# Video_out.net
KiCad netlist of a schematic drawn in Altium Designer
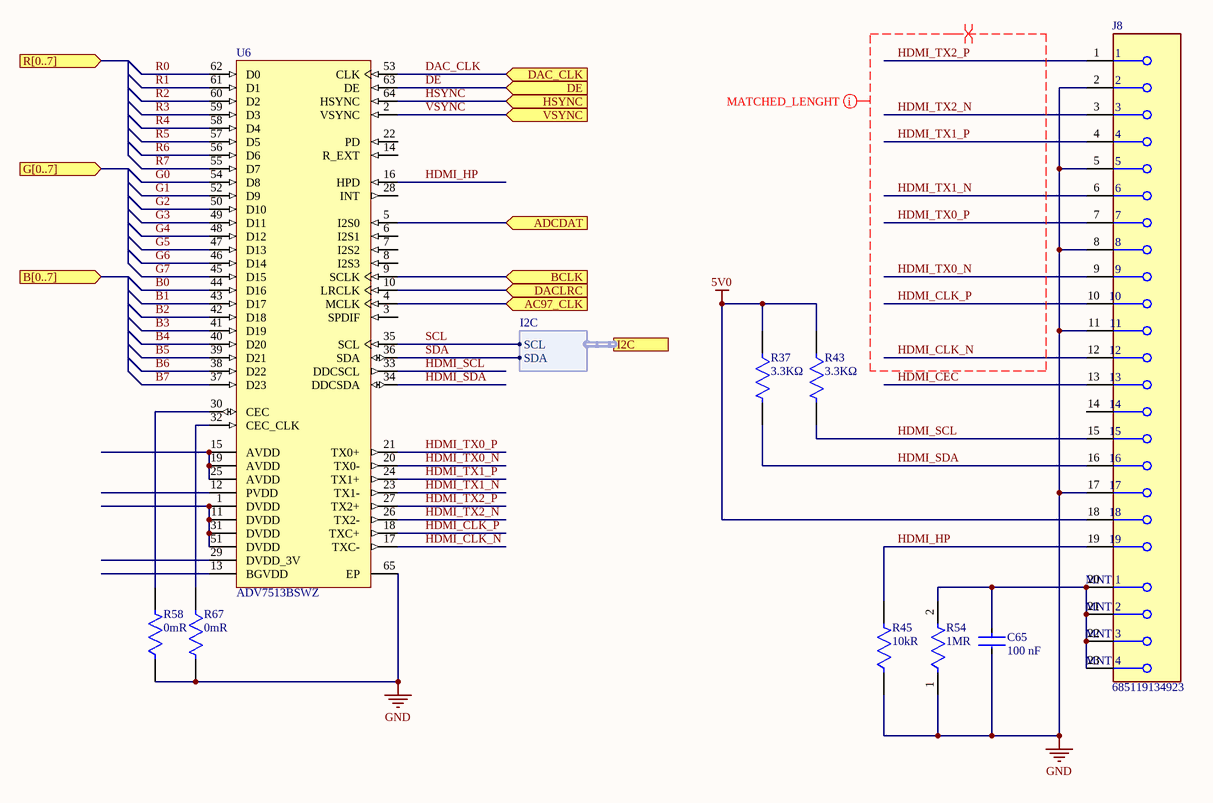
[diagram p0: Video out.SchDoc]

(export (version "E")
  (design (tool "Eeschema 10.0.6"))
  (components
    (comp (ref "C65")
      (value "CC0805KRX7R9BB104")
      (footprint "FP-CC0805-0_85-IPC_A")
      (description "CAP CER 0.1UF 50V X7R 0805")
      (fields (field (name "CAPACITANCE") "100 nF") (field (name "MANUFACTURER") "Yageo"))
      (libsource (lib "SchLib") (part "CMP-2100-03606-3"))
    )
    (comp (ref "J8")
      (value "685119134923")
      (footprint "FP-685119134923-MFG")
      (description "CONN RCPT HDMI 19POS SMD R/A")
      (libsource (lib "Altium Content Vault") (part "e5ff4299a1c525cc9972ed96ca0291b"))
    )
    (comp (ref "R37")
      (value "RT0805FRE073K3L")
      (footprint "FP-RT0805-IPC_A")
      (description "RES SMD 3.3K OHM 1% 1/8W 0805")
      (fields (field (name "MANUFACTURER") "Yageo") (field (name "RESISTANCE") "3.3KΩ"))
      (libsource (lib "SchLib") (part "CMP-03412-025935-1"))
    )
    (comp (ref "R43")
      (value "RT0805FRE073K3L")
      (footprint "FP-RT0805-IPC_A")
      (description "RES SMD 3.3K OHM 1% 1/8W 0805")
      (fields (field (name "MANUFACTURER") "Yageo") (field (name "RESISTANCE") "3.3KΩ"))
      (libsource (lib "SchLib") (part "CMP-03412-025935-1"))
    )
    (comp (ref "R45")
      (value "CR0805-JW-103ELF")
      (footprint "FP-CR0805-IPC_A")
      (description "Thick Film Chip Resistors 0805 10kΩ 0.125W 5% 200ppm/°C")
      (fields (field (name "RESISTANCE") "10kR") (field (name "MANUFACTURER") "Bourns"))
      (libsource (lib "SchLib") (part "CMP-07231-003873-1"))
    )
    (comp (ref "R54")
      (value "ERJ-6ENF1004V")
      (footprint "FP-ERJ6EN-IPC_A")
      (description "RES SMD 1M OHM 1% 1/8W 0805")
      (fields (field (name "RESISTANCE") "1MR") (field (name "TOLERANCE") "1%"))
      (libsource (lib "Altium Content Vault") (part "1029c3af85768c4190bb7ad29bc67b5"))
    )
    (comp (ref "R58")
      (value "CR0805-J/-000ELF")
      (footprint "FP-CR0805-IPC_A")
      (description "Thick Film Chip Resistors 0805 0Ω 0.125W 5%")
      (fields (field (name "RESISTANCE") "0mR") (field (name "MANUFACTURER") "Bourns"))
      (libsource (lib "SchLib") (part "CMP-07231-004348-1"))
    )
    (comp (ref "R67")
      (value "CR0805-J/-000ELF")
      (footprint "FP-CR0805-IPC_A")
      (description "Thick Film Chip Resistors 0805 0Ω 0.125W 5%")
      (fields (field (name "RESISTANCE") "0mR") (field (name "MANUFACTURER") "Bourns"))
      (libsource (lib "SchLib") (part "CMP-07231-004348-1"))
    )
    (comp (ref "U6")
      (value "ADV7513BSWZ")
      (footprint "ADI-LQFP-64_M")
      (description "High Performance HDMI Transmitter, 165 MHz, 1.8 to 3.3 V, -25 to 85 degC, 64-Pin LQFP, RoHS, Tray")
      (fields (field (name "MANUFACTURER") "AnalogDevicesInc."))
      (libsource (lib "Altium Content Vault") (part "ADI-ADV7513BSWZ-LQFP-64"))
    )
  )
  (nets
    (net (code "2") (name "/AC97_CLK") (class "Default")
      (node (ref "U6") (pin "4") (pinfunction "MCLK_4") (pintype "input"))
    )
    (net (code "3") (name "/ADCDAT") (class "Default")
      (node (ref "U6") (pin "5") (pinfunction "I2S0_5") (pintype "input"))
    )
    (net (code "4") (name "/B0") (class "Default")
      (node (ref "U6") (pin "44") (pinfunction "D16_44") (pintype "input"))
    )
    (net (code "5") (name "/B1") (class "Default")
      (node (ref "U6") (pin "43") (pinfunction "D17_43") (pintype "input"))
    )
    (net (code "6") (name "/B2") (class "Default")
      (node (ref "U6") (pin "42") (pinfunction "D18_42") (pintype "input"))
    )
    (net (code "7") (name "/B3") (class "Default")
      (node (ref "U6") (pin "41") (pinfunction "D19_41") (pintype "input"))
    )
    (net (code "8") (name "/B4") (class "Default")
      (node (ref "U6") (pin "40") (pinfunction "D20_40") (pintype "input"))
    )
    (net (code "9") (name "/B5") (class "Default")
      (node (ref "U6") (pin "39") (pinfunction "D21_39") (pintype "input"))
    )
    (net (code "10") (name "/B6") (class "Default")
      (node (ref "U6") (pin "38") (pinfunction "D22_38") (pintype "input"))
    )
    (net (code "11") (name "/B7") (class "Default")
      (node (ref "U6") (pin "37") (pinfunction "D23_37") (pintype "input"))
    )
    (net (code "12") (name "/BCLK") (class "Default")
      (node (ref "U6") (pin "9") (pinfunction "SCLK_9") (pintype "input"))
    )
    (net (code "14") (name "/DACLRC") (class "Default")
      (node (ref "U6") (pin "10") (pinfunction "LRCLK_10") (pintype "input"))
    )
    (net (code "15") (name "/DAC_CLK") (class "Default")
      (node (ref "U6") (pin "53") (pinfunction "CLK_53") (pintype "input"))
    )
    (net (code "16") (name "/DE") (class "Default")
      (node (ref "U6") (pin "63") (pinfunction "DE_63") (pintype "input"))
    )
    (net (code "17") (name "/G0") (class "Default")
      (node (ref "U6") (pin "54") (pinfunction "D8_54") (pintype "input"))
    )
    (net (code "18") (name "/G1") (class "Default")
      (node (ref "U6") (pin "52") (pinfunction "D9_52") (pintype "input"))
    )
    (net (code "19") (name "/G2") (class "Default")
      (node (ref "U6") (pin "50") (pinfunction "D10_50") (pintype "input"))
    )
    (net (code "20") (name "/G3") (class "Default")
      (node (ref "U6") (pin "49") (pinfunction "D11_49") (pintype "input"))
    )
    (net (code "21") (name "/G4") (class "Default")
      (node (ref "U6") (pin "48") (pinfunction "D12_48") (pintype "input"))
    )
    (net (code "22") (name "/G5") (class "Default")
      (node (ref "U6") (pin "47") (pinfunction "D13_47") (pintype "input"))
    )
    (net (code "23") (name "/G6") (class "Default")
      (node (ref "U6") (pin "46") (pinfunction "D14_46") (pintype "input"))
    )
    (net (code "24") (name "/G7") (class "Default")
      (node (ref "U6") (pin "45") (pinfunction "D15_45") (pintype "input"))
    )
    (net (code "26") (name "/HDMI_CEC") (class "Default")
      (node (ref "J8") (pin "13") (pinfunction "13_13") (pintype "passive"))
    )
    (net (code "27") (name "/HDMI_CLK_N") (class "Default")
      (node (ref "J8") (pin "12") (pinfunction "12_12") (pintype "passive"))
      (node (ref "U6") (pin "17") (pinfunction "TXC-_17") (pintype "output"))
    )
    (net (code "28") (name "/HDMI_CLK_P") (class "Default")
      (node (ref "J8") (pin "10") (pinfunction "10_10") (pintype "passive"))
      (node (ref "U6") (pin "18") (pinfunction "TXC+_18") (pintype "output"))
    )
    (net (code "29") (name "/HDMI_HP") (class "Default")
      (node (ref "J8") (pin "19") (pinfunction "19_19") (pintype "passive"))
      (node (ref "R45") (pin "2") (pinfunction "2_2") (pintype "passive"))
      (node (ref "U6") (pin "16") (pinfunction "HPD_16") (pintype "input"))
    )
    (net (code "30") (name "/HDMI_SCL") (class "Default")
      (node (ref "J8") (pin "15") (pinfunction "15_15") (pintype "passive"))
      (node (ref "R43") (pin "2") (pinfunction "2_2") (pintype "passive"))
      (node (ref "U6") (pin "33") (pinfunction "DDCSCL_33") (pintype "output"))
    )
    (net (code "31") (name "/HDMI_SDA") (class "Default")
      (node (ref "J8") (pin "16") (pinfunction "16_16") (pintype "passive"))
      (node (ref "R37") (pin "2") (pinfunction "2_2") (pintype "passive"))
      (node (ref "U6") (pin "34") (pinfunction "DDCSDA_34") (pintype "bidirectional"))
    )
    (net (code "32") (name "/HDMI_TX0_N") (class "Default")
      (node (ref "J8") (pin "9") (pinfunction "9_9") (pintype "passive"))
      (node (ref "U6") (pin "20") (pinfunction "TX0-_20") (pintype "output"))
    )
    (net (code "33") (name "/HDMI_TX0_P") (class "Default")
      (node (ref "J8") (pin "7") (pinfunction "7_7") (pintype "passive"))
      (node (ref "U6") (pin "21") (pinfunction "TX0+_21") (pintype "output"))
    )
    (net (code "34") (name "/HDMI_TX1_N") (class "Default")
      (node (ref "J8") (pin "6") (pinfunction "6_6") (pintype "passive"))
      (node (ref "U6") (pin "23") (pinfunction "TX1-_23") (pintype "output"))
    )
    (net (code "35") (name "/HDMI_TX1_P") (class "Default")
      (node (ref "J8") (pin "4") (pinfunction "4_4") (pintype "passive"))
      (node (ref "U6") (pin "24") (pinfunction "TX1+_24") (pintype "output"))
    )
    (net (code "36") (name "/HDMI_TX2_N") (class "Default")
      (node (ref "J8") (pin "3") (pinfunction "3_3") (pintype "passive"))
      (node (ref "U6") (pin "26") (pinfunction "TX2-_26") (pintype "output"))
    )
    (net (code "37") (name "/HDMI_TX2_P") (class "Default")
      (node (ref "J8") (pin "1") (pinfunction "1_1") (pintype "passive"))
      (node (ref "U6") (pin "27") (pinfunction "TX2+_27") (pintype "output"))
    )
    (net (code "38") (name "/HSYNC") (class "Default")
      (node (ref "U6") (pin "64") (pinfunction "HSYNC_64") (pintype "input"))
    )
    (net (code "39") (name "/R0") (class "Default")
      (node (ref "U6") (pin "62") (pinfunction "D0_62") (pintype "input"))
    )
    (net (code "40") (name "/R1") (class "Default")
      (node (ref "U6") (pin "61") (pinfunction "D1_61") (pintype "input"))
    )
    (net (code "41") (name "/R2") (class "Default")
      (node (ref "U6") (pin "60") (pinfunction "D2_60") (pintype "input"))
    )
    (net (code "42") (name "/R3") (class "Default")
      (node (ref "U6") (pin "59") (pinfunction "D3_59") (pintype "input"))
    )
    (net (code "43") (name "/R4") (class "Default")
      (node (ref "U6") (pin "58") (pinfunction "D4_58") (pintype "input"))
    )
    (net (code "44") (name "/R5") (class "Default")
      (node (ref "U6") (pin "57") (pinfunction "D5_57") (pintype "input"))
    )
    (net (code "45") (name "/R6") (class "Default")
      (node (ref "U6") (pin "56") (pinfunction "D6_56") (pintype "input"))
    )
    (net (code "46") (name "/R7") (class "Default")
      (node (ref "U6") (pin "55") (pinfunction "D7_55") (pintype "input"))
    )
    (net (code "48") (name "/SCL") (class "Default")
      (node (ref "U6") (pin "35") (pinfunction "SCL_35") (pintype "input"))
    )
    (net (code "49") (name "/SDA") (class "Default")
      (node (ref "U6") (pin "36") (pinfunction "SDA_36") (pintype "bidirectional"))
    )
    (net (code "50") (name "/VSYNC") (class "Default")
      (node (ref "U6") (pin "2") (pinfunction "VSYNC_2") (pintype "input"))
    )
    (net (code "52") (name "5V0") (class "Default")
      (node (ref "J8") (pin "18") (pinfunction "18_18") (pintype "passive"))
      (node (ref "R37") (pin "1") (pinfunction "1_1") (pintype "passive"))
      (node (ref "R43") (pin "1") (pinfunction "1_1") (pintype "passive"))
    )
    (net (code "53") (name "GND") (class "Default")
      (node (ref "C65") (pin "2") (pinfunction "2_2") (pintype "passive"))
      (node (ref "J8") (pin "11") (pinfunction "11_11") (pintype "passive"))
      (node (ref "J8") (pin "17") (pinfunction "17_17") (pintype "passive"))
      (node (ref "J8") (pin "2") (pinfunction "2_2") (pintype "passive"))
      (node (ref "J8") (pin "5") (pinfunction "5_5") (pintype "passive"))
      (node (ref "J8") (pin "8") (pinfunction "8_8") (pintype "passive"))
      (node (ref "R45") (pin "1") (pinfunction "1_1") (pintype "passive"))
      (node (ref "R54") (pin "1") (pinfunction "1_1") (pintype "passive"))
      (node (ref "R58") (pin "1") (pinfunction "1_1") (pintype "passive"))
      (node (ref "R67") (pin "2") (pinfunction "2_2") (pintype "passive"))
      (node (ref "U6") (pin "65") (pinfunction "EP_65") (pintype "power_in"))
    )
    (net (code "54") (name "Net-(J8-MNT_1)") (class "Default")
      (node (ref "C65") (pin "1") (pinfunction "1_1") (pintype "passive"))
      (node (ref "J8") (pin "20") (pinfunction "MNT_1_20") (pintype "passive"))
      (node (ref "J8") (pin "21") (pinfunction "MNT_2_21") (pintype "passive"))
      (node (ref "J8") (pin "22") (pinfunction "MNT_3_22") (pintype "passive"))
      (node (ref "J8") (pin "23") (pinfunction "MNT_4_23") (pintype "passive"))
      (node (ref "R54") (pin "2") (pinfunction "2_2") (pintype "passive"))
    )
    (net (code "55") (name "Net-(U6-AVDD-Pad15)") (class "Default")
      (node (ref "U6") (pin "15") (pinfunction "AVDD_15") (pintype "power_in"))
      (node (ref "U6") (pin "19") (pinfunction "AVDD_19") (pintype "power_in"))
      (node (ref "U6") (pin "25") (pinfunction "AVDD_25") (pintype "power_in"))
    )
    (net (code "56") (name "Net-(U6-CEC)") (class "Default")
      (node (ref "R58") (pin "2") (pinfunction "2_2") (pintype "passive"))
      (node (ref "U6") (pin "30") (pinfunction "CEC_30") (pintype "bidirectional"))
    )
    (net (code "57") (name "Net-(U6-CEC_CLK)") (class "Default")
      (node (ref "R67") (pin "1") (pinfunction "1_1") (pintype "passive"))
      (node (ref "U6") (pin "32") (pinfunction "CEC_CLK_32") (pintype "input"))
    )
    (net (code "58") (name "Net-(U6-DVDD-Pad1)") (class "Default")
      (node (ref "U6") (pin "1") (pinfunction "DVDD_1") (pintype "power_in"))
      (node (ref "U6") (pin "11") (pinfunction "DVDD_11") (pintype "power_in"))
      (node (ref "U6") (pin "31") (pinfunction "DVDD_31") (pintype "power_in"))
      (node (ref "U6") (pin "51") (pinfunction "DVDD_51") (pintype "power_in"))
    )
    (net (code "59") (name "unconnected-(J8-Pad14)") (class "Default")
      (node (ref "J8") (pin "14") (pinfunction "14_14") (pintype "passive"))
    )
    (net (code "60") (name "unconnected-(U6-BGVDD-Pad13)") (class "Default")
      (node (ref "U6") (pin "13") (pinfunction "BGVDD_13") (pintype "power_in"))
    )
    (net (code "61") (name "unconnected-(U6-DVDD_3V-Pad29)") (class "Default")
      (node (ref "U6") (pin "29") (pinfunction "DVDD_3V_29") (pintype "power_in"))
    )
    (net (code "62") (name "unconnected-(U6-I2S1-Pad6)") (class "Default")
      (node (ref "U6") (pin "6") (pinfunction "I2S1_6") (pintype "input"))
    )
    (net (code "63") (name "unconnected-(U6-I2S2-Pad7)") (class "Default")
      (node (ref "U6") (pin "7") (pinfunction "I2S2_7") (pintype "input"))
    )
    (net (code "64") (name "unconnected-(U6-I2S3-Pad8)") (class "Default")
      (node (ref "U6") (pin "8") (pinfunction "I2S3_8") (pintype "input"))
    )
    (net (code "65") (name "unconnected-(U6-INT-Pad28)") (class "Default")
      (node (ref "U6") (pin "28") (pinfunction "INT_28") (pintype "output"))
    )
    (net (code "66") (name "unconnected-(U6-PD-Pad22)") (class "Default")
      (node (ref "U6") (pin "22") (pinfunction "PD_22") (pintype "input"))
    )
    (net (code "67") (name "unconnected-(U6-PVDD-Pad12)") (class "Default")
      (node (ref "U6") (pin "12") (pinfunction "PVDD_12") (pintype "power_in"))
    )
    (net (code "68") (name "unconnected-(U6-R_EXT-Pad14)") (class "Default")
      (node (ref "U6") (pin "14") (pinfunction "R_EXT_14") (pintype "input"))
    )
    (net (code "69") (name "unconnected-(U6-SPDIF-Pad3)") (class "Default")
      (node (ref "U6") (pin "3") (pinfunction "SPDIF_3") (pintype "input"))
    )
  )
)
